# design.net
KiCad netlist of a schematic drawn in Altium Designer
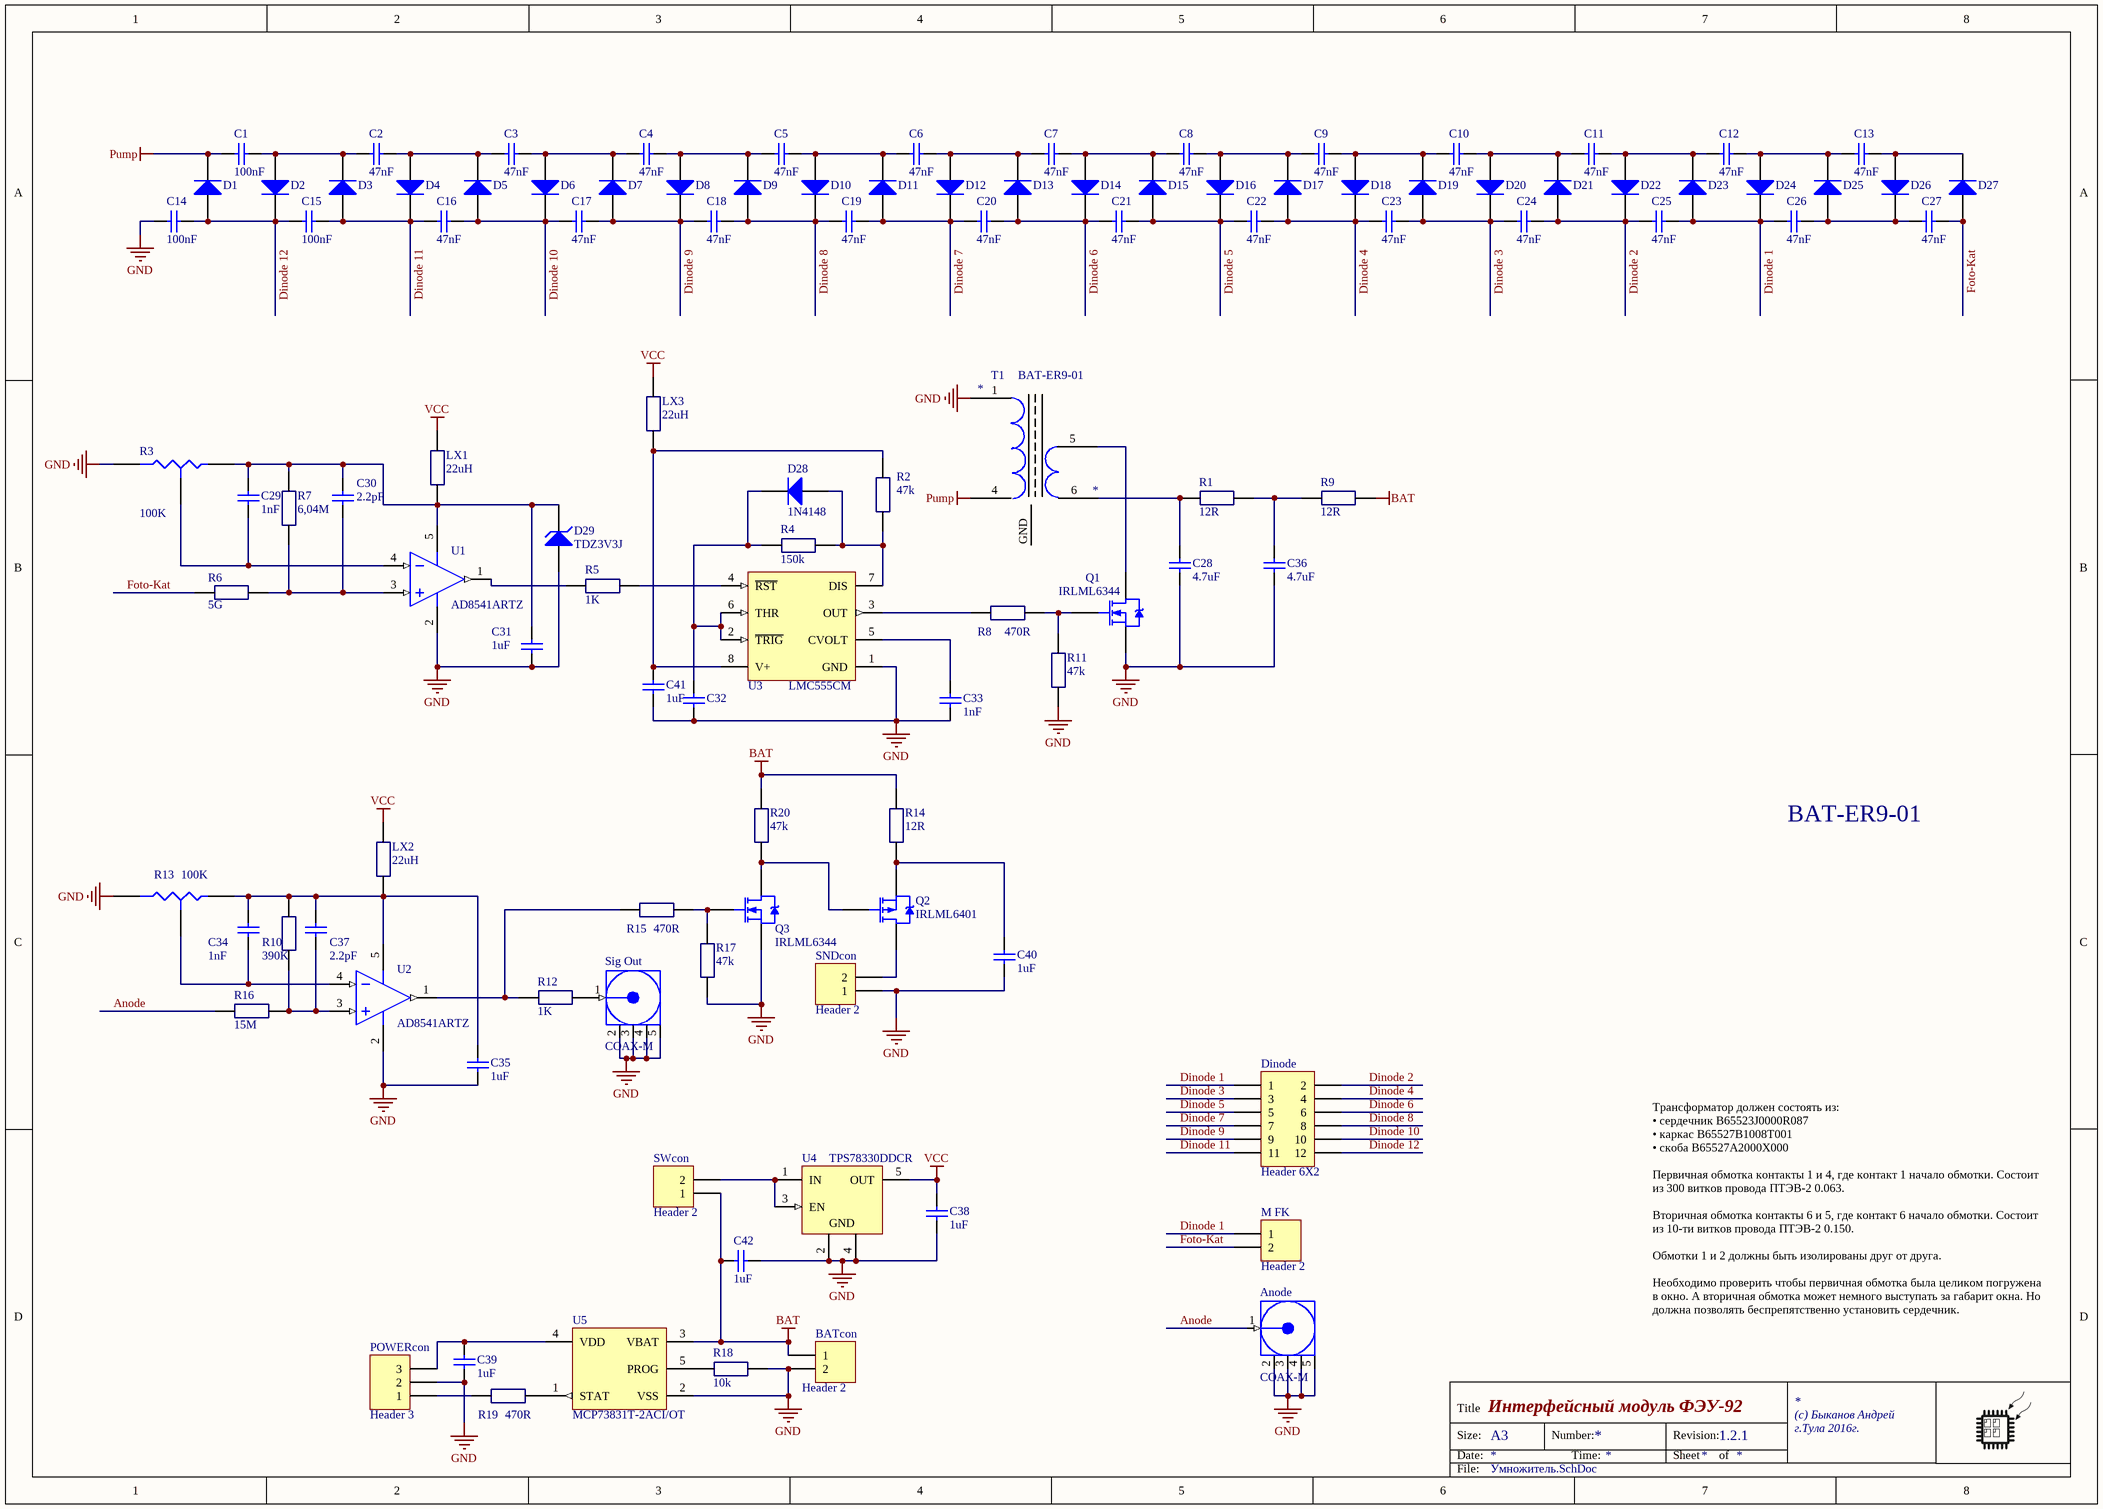
[diagram p0: Умножитель.SchDoc]

(export (version "E")
  (design (tool "Eeschema 10.0.6"))
  (components
    (comp (ref "Anode")
      (value "COAX-M")
      (footprint "MMCX2.54-V5")
      (description "RF Coaxial PCB Connector, MMCX; Thru-Hole, Vertical Mount Plug,  50 Ohm Impedance")
      (fields (field (name "PUBLISHER") "Altium Limited"))
      (libsource (lib "Miscellaneous Connectors") (part "COAX-M"))
    )
    (comp (ref "BATcon")
      (value "Header 2")
      (footprint "LIR2430")
      (description "Header, 2-Pin")
      (fields (field (name "PUBLISHER") "Altium Limited"))
      (libsource (lib "") (part "Header 2_1"))
    )
    (comp (ref "C1")
      (value "100nF")
      (footprint "Miscellaneous Devices:C1206")
      (description "Capacitor (Semiconductor SIM Model)")
      (fields (field (name "PUBLISHER") "Altium Limited"))
      (libsource (lib "Miscellaneous Devices") (part "Cap Semi"))
    )
    (comp (ref "C2")
      (value "47nF")
      (footprint "0805_CAP")
      (description "Capacitor (Semiconductor SIM Model)")
      (fields (field (name "PUBLISHER") "Altium Limited"))
      (libsource (lib "Miscellaneous Devices") (part "Cap Semi"))
    )
    (comp (ref "C3")
      (value "47nF")
      (footprint "0805_CAP")
      (description "Capacitor (Semiconductor SIM Model)")
      (fields (field (name "PUBLISHER") "Altium Limited"))
      (libsource (lib "Miscellaneous Devices") (part "Cap Semi"))
    )
    (comp (ref "C4")
      (value "47nF")
      (footprint "0805_CAP")
      (description "Capacitor (Semiconductor SIM Model)")
      (fields (field (name "PUBLISHER") "Altium Limited"))
      (libsource (lib "Miscellaneous Devices") (part "Cap Semi"))
    )
    (comp (ref "C5")
      (value "47nF")
      (footprint "0805_CAP")
      (description "Capacitor (Semiconductor SIM Model)")
      (fields (field (name "PUBLISHER") "Altium Limited"))
      (libsource (lib "Miscellaneous Devices") (part "Cap Semi"))
    )
    (comp (ref "C6")
      (value "47nF")
      (footprint "0805_CAP")
      (description "Capacitor (Semiconductor SIM Model)")
      (fields (field (name "PUBLISHER") "Altium Limited"))
      (libsource (lib "Miscellaneous Devices") (part "Cap Semi"))
    )
    (comp (ref "C7")
      (value "47nF")
      (footprint "0805_CAP")
      (description "Capacitor (Semiconductor SIM Model)")
      (fields (field (name "PUBLISHER") "Altium Limited"))
      (libsource (lib "Miscellaneous Devices") (part "Cap Semi"))
    )
    (comp (ref "C8")
      (value "47nF")
      (footprint "0805_CAP")
      (description "Capacitor (Semiconductor SIM Model)")
      (fields (field (name "PUBLISHER") "Altium Limited"))
      (libsource (lib "Miscellaneous Devices") (part "Cap Semi"))
    )
    (comp (ref "C9")
      (value "47nF")
      (footprint "0805_CAP")
      (description "Capacitor (Semiconductor SIM Model)")
      (fields (field (name "PUBLISHER") "Altium Limited"))
      (libsource (lib "Miscellaneous Devices") (part "Cap Semi"))
    )
    (comp (ref "C10")
      (value "47nF")
      (footprint "0805_CAP")
      (description "Capacitor (Semiconductor SIM Model)")
      (fields (field (name "PUBLISHER") "Altium Limited"))
      (libsource (lib "Miscellaneous Devices") (part "Cap Semi"))
    )
    (comp (ref "C11")
      (value "47nF")
      (footprint "0805_CAP")
      (description "Capacitor (Semiconductor SIM Model)")
      (fields (field (name "PUBLISHER") "Altium Limited"))
      (libsource (lib "Miscellaneous Devices") (part "Cap Semi"))
    )
    (comp (ref "C12")
      (value "47nF")
      (footprint "0805_CAP")
      (description "Capacitor (Semiconductor SIM Model)")
      (fields (field (name "PUBLISHER") "Altium Limited"))
      (libsource (lib "Miscellaneous Devices") (part "Cap Semi"))
    )
    (comp (ref "C13")
      (value "47nF")
      (footprint "0805_CAP")
      (description "Capacitor (Semiconductor SIM Model)")
      (fields (field (name "PUBLISHER") "Altium Limited"))
      (libsource (lib "Miscellaneous Devices") (part "Cap Semi"))
    )
    (comp (ref "C14")
      (value "100nF")
      (footprint "Miscellaneous Devices:C1206")
      (description "Capacitor (Semiconductor SIM Model)")
      (fields (field (name "PUBLISHER") "Altium Limited"))
      (libsource (lib "Miscellaneous Devices") (part "Cap Semi"))
    )
    (comp (ref "C15")
      (value "100nF")
      (footprint "Miscellaneous Devices:C1206")
      (description "Capacitor (Semiconductor SIM Model)")
      (fields (field (name "PUBLISHER") "Altium Limited"))
      (libsource (lib "Miscellaneous Devices") (part "Cap Semi"))
    )
    (comp (ref "C16")
      (value "47nF")
      (footprint "0805_CAP")
      (description "Capacitor (Semiconductor SIM Model)")
      (fields (field (name "PUBLISHER") "Altium Limited"))
      (libsource (lib "Miscellaneous Devices") (part "Cap Semi"))
    )
    (comp (ref "C17")
      (value "47nF")
      (footprint "0805_CAP")
      (description "Capacitor (Semiconductor SIM Model)")
      (fields (field (name "PUBLISHER") "Altium Limited"))
      (libsource (lib "Miscellaneous Devices") (part "Cap Semi"))
    )
    (comp (ref "C18")
      (value "47nF")
      (footprint "0805_CAP")
      (description "Capacitor (Semiconductor SIM Model)")
      (fields (field (name "PUBLISHER") "Altium Limited"))
      (libsource (lib "Miscellaneous Devices") (part "Cap Semi"))
    )
    (comp (ref "C19")
      (value "47nF")
      (footprint "0805_CAP")
      (description "Capacitor (Semiconductor SIM Model)")
      (fields (field (name "PUBLISHER") "Altium Limited"))
      (libsource (lib "Miscellaneous Devices") (part "Cap Semi"))
    )
    (comp (ref "C20")
      (value "47nF")
      (footprint "0805_CAP")
      (description "Capacitor (Semiconductor SIM Model)")
      (fields (field (name "PUBLISHER") "Altium Limited"))
      (libsource (lib "Miscellaneous Devices") (part "Cap Semi"))
    )
    (comp (ref "C21")
      (value "47nF")
      (footprint "0805_CAP")
      (description "Capacitor (Semiconductor SIM Model)")
      (fields (field (name "PUBLISHER") "Altium Limited"))
      (libsource (lib "Miscellaneous Devices") (part "Cap Semi"))
    )
    (comp (ref "C22")
      (value "47nF")
      (footprint "0805_CAP")
      (description "Capacitor (Semiconductor SIM Model)")
      (fields (field (name "PUBLISHER") "Altium Limited"))
      (libsource (lib "Miscellaneous Devices") (part "Cap Semi"))
    )
    (comp (ref "C23")
      (value "47nF")
      (footprint "0805_CAP")
      (description "Capacitor (Semiconductor SIM Model)")
      (fields (field (name "PUBLISHER") "Altium Limited"))
      (libsource (lib "Miscellaneous Devices") (part "Cap Semi"))
    )
    (comp (ref "C24")
      (value "47nF")
      (footprint "0805_CAP")
      (description "Capacitor (Semiconductor SIM Model)")
      (fields (field (name "PUBLISHER") "Altium Limited"))
      (libsource (lib "Miscellaneous Devices") (part "Cap Semi"))
    )
    (comp (ref "C25")
      (value "47nF")
      (footprint "0805_CAP")
      (description "Capacitor (Semiconductor SIM Model)")
      (fields (field (name "PUBLISHER") "Altium Limited"))
      (libsource (lib "Miscellaneous Devices") (part "Cap Semi"))
    )
    (comp (ref "C26")
      (value "47nF")
      (footprint "0805_CAP")
      (description "Capacitor (Semiconductor SIM Model)")
      (fields (field (name "PUBLISHER") "Altium Limited"))
      (libsource (lib "Miscellaneous Devices") (part "Cap Semi"))
    )
    (comp (ref "C27")
      (value "47nF")
      (footprint "0805_CAP")
      (description "Capacitor (Semiconductor SIM Model)")
      (fields (field (name "PUBLISHER") "Altium Limited"))
      (libsource (lib "Miscellaneous Devices") (part "Cap Semi"))
    )
    (comp (ref "C28")
      (value "4.7uF")
      (footprint "Miscellaneous Devices:C1206")
      (description "Capacitor (Semiconductor SIM Model)")
      (fields (field (name "PUBLISHER") "Altium Limited"))
      (libsource (lib "Miscellaneous Devices") (part "Cap Semi"))
    )
    (comp (ref "C29")
      (value "1nF")
      (footprint "1608[0603]_CAP")
      (description "Capacitor (Semiconductor SIM Model)")
      (fields (field (name "PUBLISHER") "Altium Limited"))
      (libsource (lib "Miscellaneous Devices") (part "Cap Semi"))
    )
    (comp (ref "C30")
      (value "2.2pF")
      (footprint "1608[0603]_CAP")
      (description "Capacitor (Semiconductor SIM Model)")
      (fields (field (name "PUBLISHER") "Altium Limited"))
      (libsource (lib "Miscellaneous Devices") (part "Cap Semi"))
    )
    (comp (ref "C31")
      (value "1uF")
      (footprint "1608[0603]_CAP")
      (description "Capacitor (Semiconductor SIM Model)")
      (fields (field (name "PUBLISHER") "Altium Limited"))
      (libsource (lib "Miscellaneous Devices") (part "Cap Semi"))
    )
    (comp (ref "C32")
      (value "220pF")
      (footprint "1608[0603]_CAP")
      (description "Capacitor (Semiconductor SIM Model)")
      (fields (field (name "PUBLISHER") "Altium Limited"))
      (libsource (lib "Miscellaneous Devices") (part "Cap Semi"))
    )
    (comp (ref "C33")
      (value "1nF")
      (footprint "1608[0603]_CAP")
      (description "Capacitor (Semiconductor SIM Model)")
      (fields (field (name "PUBLISHER") "Altium Limited"))
      (libsource (lib "Miscellaneous Devices") (part "Cap Semi"))
    )
    (comp (ref "C34")
      (value "1nF")
      (footprint "1608[0603]_CAP")
      (description "Capacitor (Semiconductor SIM Model)")
      (fields (field (name "PUBLISHER") "Altium Limited"))
      (libsource (lib "Miscellaneous Devices") (part "Cap Semi"))
    )
    (comp (ref "C35")
      (value "1uF")
      (footprint "1608[0603]_CAP")
      (description "Capacitor (Semiconductor SIM Model)")
      (fields (field (name "PUBLISHER") "Altium Limited"))
      (libsource (lib "Miscellaneous Devices") (part "Cap Semi"))
    )
    (comp (ref "C36")
      (value "4.7uF")
      (footprint "Miscellaneous Devices:C1206")
      (description "Capacitor (Semiconductor SIM Model)")
      (fields (field (name "PUBLISHER") "Altium Limited"))
      (libsource (lib "Miscellaneous Devices") (part "Cap Semi"))
    )
    (comp (ref "C37")
      (value "2.2pF")
      (footprint "1608[0603]_CAP")
      (description "Capacitor (Semiconductor SIM Model)")
      (fields (field (name "PUBLISHER") "Altium Limited"))
      (libsource (lib "Miscellaneous Devices") (part "Cap Semi"))
    )
    (comp (ref "C38")
      (value "1uF")
      (footprint "1608[0603]_CAP")
      (description "Capacitor (Semiconductor SIM Model)")
      (fields (field (name "PUBLISHER") "Altium Limited"))
      (libsource (lib "Miscellaneous Devices") (part "Cap Semi"))
    )
    (comp (ref "C39")
      (value "1uF")
      (footprint "1608[0603]_CAP")
      (description "Capacitor (Semiconductor SIM Model)")
      (fields (field (name "PUBLISHER") "Altium Limited"))
      (libsource (lib "Miscellaneous Devices") (part "Cap Semi"))
    )
    (comp (ref "C40")
      (value "1uF")
      (footprint "1608[0603]_CAP")
      (description "Capacitor (Semiconductor SIM Model)")
      (fields (field (name "PUBLISHER") "Altium Limited"))
      (libsource (lib "Miscellaneous Devices") (part "Cap Semi"))
    )
    (comp (ref "C41")
      (value "1uF")
      (footprint "1608[0603]_CAP")
      (description "Capacitor (Semiconductor SIM Model)")
      (fields (field (name "PUBLISHER") "Altium Limited"))
      (libsource (lib "Miscellaneous Devices") (part "Cap Semi"))
    )
    (comp (ref "C42")
      (value "1uF")
      (footprint "1608[0603]_CAP")
      (description "Capacitor (Semiconductor SIM Model)")
      (fields (field (name "PUBLISHER") "Altium Limited"))
      (libsource (lib "Miscellaneous Devices") (part "Cap Semi"))
    )
    (comp (ref "D1")
      (value "~")
      (footprint "DA2JF8100L")
      (description "Default Diode")
      (fields (field (name "PUBLISHER") "Altium Limited"))
      (libsource (lib "Miscellaneous Devices") (part "Diode"))
    )
    (comp (ref "D2")
      (value "~")
      (footprint "DA2JF8100L")
      (description "Default Diode")
      (fields (field (name "PUBLISHER") "Altium Limited"))
      (libsource (lib "Miscellaneous Devices") (part "Diode"))
    )
    (comp (ref "D3")
      (value "~")
      (footprint "DA2JF8100L")
      (description "Default Diode")
      (fields (field (name "PUBLISHER") "Altium Limited"))
      (libsource (lib "Miscellaneous Devices") (part "Diode"))
    )
    (comp (ref "D4")
      (value "~")
      (footprint "DA2JF8100L")
      (description "Default Diode")
      (fields (field (name "PUBLISHER") "Altium Limited"))
      (libsource (lib "Miscellaneous Devices") (part "Diode"))
    )
    (comp (ref "D5")
      (value "~")
      (footprint "DA2JF8100L")
      (description "Default Diode")
      (fields (field (name "PUBLISHER") "Altium Limited"))
      (libsource (lib "Miscellaneous Devices") (part "Diode"))
    )
    (comp (ref "D6")
      (value "~")
      (footprint "DA2JF8100L")
      (description "Default Diode")
      (fields (field (name "PUBLISHER") "Altium Limited"))
      (libsource (lib "Miscellaneous Devices") (part "Diode"))
    )
    (comp (ref "D7")
      (value "~")
      (footprint "DA2JF8100L")
      (description "Default Diode")
      (fields (field (name "PUBLISHER") "Altium Limited"))
      (libsource (lib "Miscellaneous Devices") (part "Diode"))
    )
    (comp (ref "D8")
      (value "~")
      (footprint "DA2JF8100L")
      (description "Default Diode")
      (fields (field (name "PUBLISHER") "Altium Limited"))
      (libsource (lib "Miscellaneous Devices") (part "Diode"))
    )
    (comp (ref "D9")
      (value "~")
      (footprint "DA2JF8100L")
      (description "Default Diode")
      (fields (field (name "PUBLISHER") "Altium Limited"))
      (libsource (lib "Miscellaneous Devices") (part "Diode"))
    )
    (comp (ref "D10")
      (value "~")
      (footprint "DA2JF8100L")
      (description "Default Diode")
      (fields (field (name "PUBLISHER") "Altium Limited"))
      (libsource (lib "Miscellaneous Devices") (part "Diode"))
    )
    (comp (ref "D11")
      (value "~")
      (footprint "DA2JF8100L")
      (description "Default Diode")
      (fields (field (name "PUBLISHER") "Altium Limited"))
      (libsource (lib "Miscellaneous Devices") (part "Diode"))
    )
    (comp (ref "D12")
      (value "~")
      (footprint "DA2JF8100L")
      (description "Default Diode")
      (fields (field (name "PUBLISHER") "Altium Limited"))
      (libsource (lib "Miscellaneous Devices") (part "Diode"))
    )
    (comp (ref "D13")
      (value "~")
      (footprint "DA2JF8100L")
      (description "Default Diode")
      (fields (field (name "PUBLISHER") "Altium Limited"))
      (libsource (lib "Miscellaneous Devices") (part "Diode"))
    )
    (comp (ref "D14")
      (value "~")
      (footprint "DA2JF8100L")
      (description "Default Diode")
      (fields (field (name "PUBLISHER") "Altium Limited"))
      (libsource (lib "Miscellaneous Devices") (part "Diode"))
    )
    (comp (ref "D15")
      (value "~")
      (footprint "DA2JF8100L")
      (description "Default Diode")
      (fields (field (name "PUBLISHER") "Altium Limited"))
      (libsource (lib "Miscellaneous Devices") (part "Diode"))
    )
    (comp (ref "D16")
      (value "~")
      (footprint "DA2JF8100L")
      (description "Default Diode")
      (fields (field (name "PUBLISHER") "Altium Limited"))
      (libsource (lib "Miscellaneous Devices") (part "Diode"))
    )
    (comp (ref "D17")
      (value "~")
      (footprint "DA2JF8100L")
      (description "Default Diode")
      (fields (field (name "PUBLISHER") "Altium Limited"))
      (libsource (lib "Miscellaneous Devices") (part "Diode"))
    )
    (comp (ref "D18")
      (value "~")
      (footprint "DA2JF8100L")
      (description "Default Diode")
      (fields (field (name "PUBLISHER") "Altium Limited"))
      (libsource (lib "Miscellaneous Devices") (part "Diode"))
    )
    (comp (ref "D19")
      (value "~")
      (footprint "DA2JF8100L")
      (description "Default Diode")
      (fields (field (name "PUBLISHER") "Altium Limited"))
      (libsource (lib "Miscellaneous Devices") (part "Diode"))
    )
    (comp (ref "D20")
      (value "~")
      (footprint "DA2JF8100L")
      (description "Default Diode")
      (fields (field (name "PUBLISHER") "Altium Limited"))
      (libsource (lib "Miscellaneous Devices") (part "Diode"))
    )
    (comp (ref "D21")
      (value "~")
      (footprint "DA2JF8100L")
      (description "Default Diode")
      (fields (field (name "PUBLISHER") "Altium Limited"))
      (libsource (lib "Miscellaneous Devices") (part "Diode"))
    )
    (comp (ref "D22")
      (value "~")
      (footprint "DA2JF8100L")
      (description "Default Diode")
      (fields (field (name "PUBLISHER") "Altium Limited"))
      (libsource (lib "Miscellaneous Devices") (part "Diode"))
    )
    (comp (ref "D23")
      (value "~")
      (footprint "DA2JF8100L")
      (description "Default Diode")
      (fields (field (name "PUBLISHER") "Altium Limited"))
      (libsource (lib "Miscellaneous Devices") (part "Diode"))
    )
    (comp (ref "D24")
      (value "~")
      (footprint "DA2JF8100L")
      (description "Default Diode")
      (fields (field (name "PUBLISHER") "Altium Limited"))
      (libsource (lib "Miscellaneous Devices") (part "Diode"))
    )
    (comp (ref "D25")
      (value "~")
      (footprint "DA2JF8100L")
      (description "Default Diode")
      (fields (field (name "PUBLISHER") "Altium Limited"))
      (libsource (lib "Miscellaneous Devices") (part "Diode"))
    )
    (comp (ref "D26")
      (value "~")
      (footprint "DA2JF8100L")
      (description "Default Diode")
      (fields (field (name "PUBLISHER") "Altium Limited"))
      (libsource (lib "Miscellaneous Devices") (part "Diode"))
    )
    (comp (ref "D27")
      (value "~")
      (footprint "DA2JF8100L")
      (description "Default Diode")
      (fields (field (name "PUBLISHER") "Altium Limited"))
      (libsource (lib "Miscellaneous Devices") (part "Diode"))
    )
    (comp (ref "D28")
      (value "1N4148")
      (footprint "GRZZ0002ZB-A")
      (description "Silicon Epitaxial Planar Diode for Various Detector, Modulator, Demodulator")
      (fields (field (name "PUBLISHER") "Altium Limited"))
      (libsource (lib "Renesas Diode") (part "1N4148"))
    )
    (comp (ref "D29")
      (value "TDZ3V3J")
      (footprint "SC-90")
      (description "Zener Diode")
      (fields (field (name "PUBLISHER") "Altium Limited"))
      (libsource (lib "Miscellaneous Devices") (part "D Zener"))
    )
    (comp (ref "Dinode")
      (value "Header 6X2")
      (footprint "HDR2X6")
      (description "Header, 6-Pin, Dual row")
      (fields (field (name "PUBLISHER") "Altium Limited"))
      (libsource (lib "Miscellaneous Connectors") (part "Header 6X2"))
    )
    (comp (ref "LX1")
      (value "22uH")
      (footprint "Resistor")
      (libsource (lib "Микрон-3") (part "Resistor 0805"))
    )
    (comp (ref "LX2")
      (value "22uH")
      (footprint "Resistor")
      (libsource (lib "Микрон-3") (part "Resistor 0805"))
    )
    (comp (ref "LX3")
      (value "22uH")
      (footprint "Resistor")
      (libsource (lib "Микрон-3") (part "Resistor 0805"))
    )
    (comp (ref "M FK")
      (value "Header 2")
      (footprint "HDR1X2")
      (description "Header, 2-Pin")
      (fields (field (name "PUBLISHER") "Altium Limited"))
      (libsource (lib "") (part "Header 2_1"))
    )
    (comp (ref "POWERcon")
      (value "Header 3")
      (footprint "HDR1X3")
      (description "Header, 3-Pin")
      (fields (field (name "PUBLISHER") "Altium Limited"))
      (libsource (lib "Miscellaneous Connectors") (part "Header 3"))
    )
    (comp (ref "Q1")
      (value "IRLML6344")
      (footprint "SOT-23_N")
      (description "HEXFET Power MOSFET")
      (fields (field (name "PUBLISHER") "Altium Limited"))
      (libsource (lib "IR Discrete MOSFET - Power") (part "IRLML2402"))
    )
    (comp (ref "Q2")
      (value "IRLML6401")
      (footprint "Micro3_N")
      (description "HEXFET Power MOSFET")
      (fields (field (name "PUBLISHER") "Altium Limited"))
      (libsource (lib "IR Discrete MOSFET - Power") (part "IRLML6401"))
    )
    (comp (ref "Q3")
      (value "IRLML6344")
      (footprint "SOT-23_N")
      (description "HEXFET Power MOSFET")
      (fields (field (name "PUBLISHER") "Altium Limited"))
      (libsource (lib "IR Discrete MOSFET - Power") (part "IRLML2402"))
    )
    (comp (ref "R1")
      (value "12R")
      (footprint "1608[0603]_RES")
      (libsource (lib "Микрон-3") (part "Resistor 0805"))
    )
    (comp (ref "R2")
      (value "47k")
      (footprint "1608[0603]_RES")
      (libsource (lib "Микрон-3") (part "Resistor 0805"))
    )
    (comp (ref "R3")
      (value "100K")
      (footprint "3223W")
      (description "Tapped Resistor")
      (fields (field (name "PUBLISHER") "Altium Limited"))
      (libsource (lib "Miscellaneous Devices") (part "Res Tap"))
    )
    (comp (ref "R4")
      (value "150k")
      (footprint "1608[0603]_RES")
      (libsource (lib "Микрон-3") (part "Resistor 0805"))
    )
    (comp (ref "R5")
      (value "1K")
      (footprint "1608[0603]")
      (libsource (lib "Микрон-3") (part "Resistor 0805"))
    )
    (comp (ref "R6")
      (value "5G")
      (footprint "HVF2512T5007FE")
      (libsource (lib "Микрон-3") (part "Resistor 0805"))
    )
    (comp (ref "R7")
      (value "6,04M")
      (footprint "1608[0603]")
      (libsource (lib "Микрон-3") (part "Resistor 0805"))
    )
    (comp (ref "R8")
      (value "470R")
      (footprint "1608[0603]_RES")
      (libsource (lib "Микрон-3") (part "Resistor 0805"))
    )
    (comp (ref "R9")
      (value "12R")
      (footprint "1608[0603]_RES")
      (libsource (lib "Микрон-3") (part "Resistor 0805"))
    )
    (comp (ref "R10")
      (value "390K")
      (footprint "1608[0603]")
      (libsource (lib "Микрон-3") (part "Resistor 0805"))
    )
    (comp (ref "R11")
      (value "47k")
      (footprint "1608[0603]_RES")
      (libsource (lib "Микрон-3") (part "Resistor 0805"))
    )
    (comp (ref "R12")
      (value "1K")
      (footprint "1608[0603]")
      (libsource (lib "Микрон-3") (part "Resistor 0805"))
    )
    (comp (ref "R13")
      (value "100K")
      (footprint "3223W")
      (description "Tapped Resistor")
      (fields (field (name "PUBLISHER") "Altium Limited"))
      (libsource (lib "Miscellaneous Devices") (part "Res Tap"))
    )
    (comp (ref "R14")
      (value "12R")
      (footprint "1608[0603]_RES")
      (libsource (lib "Микрон-3") (part "Resistor 0805"))
    )
    (comp (ref "R15")
      (value "470R")
      (footprint "1608[0603]_RES")
      (libsource (lib "Микрон-3") (part "Resistor 0805"))
    )
    (comp (ref "R16")
      (value "15M")
      (footprint "1608[0603]")
      (libsource (lib "Микрон-3") (part "Resistor 0805"))
    )
    (comp (ref "R17")
      (value "47k")
      (footprint "1608[0603]_RES")
      (libsource (lib "Микрон-3") (part "Resistor 0805"))
    )
    (comp (ref "R18")
      (value "10k")
      (footprint "1608[0603]_RES")
      (libsource (lib "Микрон-3") (part "Resistor 0805"))
    )
    (comp (ref "R19")
      (value "470R")
      (footprint "1608[0603]_RES")
      (libsource (lib "Микрон-3") (part "Resistor 0805"))
    )
    (comp (ref "R20")
      (value "47k")
      (footprint "1608[0603]_RES")
      (libsource (lib "Микрон-3") (part "Resistor 0805"))
    )
    (comp (ref "Sig Out")
      (value "COAX-M")
      (footprint "MMCX2.54-V5")
      (description "RF Coaxial PCB Connector, MMCX; Thru-Hole, Vertical Mount Plug,  50 Ohm Impedance")
      (fields (field (name "PUBLISHER") "Altium Limited"))
      (libsource (lib "Miscellaneous Connectors") (part "COAX-M"))
    )
    (comp (ref "SNDcon")
      (value "Header 2")
      (footprint "HDR1X2")
      (description "Header, 2-Pin")
      (fields (field (name "PUBLISHER") "Altium Limited"))
      (libsource (lib "Miscellaneous Connectors") (part "Header 2"))
    )
    (comp (ref "SWcon")
      (value "Header 2")
      (footprint "HDR1X2")
      (description "Header, 2-Pin")
      (fields (field (name "PUBLISHER") "Altium Limited"))
      (libsource (lib "Miscellaneous Connectors") (part "Header 2"))
    )
    (comp (ref "T1")
      (value "BAT-ER9-01")
      (footprint "Epcos ER9.5/5")
      (libsource (lib "My SCH library") (part "Epcos ER9.5/5"))
    )
    (comp (ref "U1")
      (value "AD8541ARTZ")
      (footprint "ADI-RJ-5_N")
      (fields
        (field (name "GENERIC PART NUMBER") "AD8541")
        (field (name "MANUFACTURER") "Analog Devices")
        (field (name "PARTNUMBER") "AD8541ARTZ-R2")
      )
      (libsource (lib "Analog Devices Operational Amplifiers") (part "AD8541ARTZ-R2"))
    )
    (comp (ref "U2")
      (value "AD8541ARTZ")
      (footprint "ADI-RJ-5_N")
      (fields
        (field (name "GENERIC PART NUMBER") "AD8541")
        (field (name "MANUFACTURER") "Analog Devices")
        (field (name "PARTNUMBER") "AD8541ARTZ-R2")
      )
      (libsource (lib "Analog Devices Operational Amplifiers") (part "AD8541ARTZ-R2"))
    )
    (comp (ref "U3")
      (value "LMC555CM")
      (footprint "M08A_N")
      (description "CMOS Timer, 8-pin Narrow SOIC")
      (fields
        (field (name "MANUFACTURER") "National Semiconductor")
        (field (name "PUBLISHER") "Altium Limited")
      )
      (libsource (lib "NSC Analog") (part "LMC555CM"))
    )
    (comp (ref "U4")
      (value "TPS78330DDCR")
      (footprint "TI-DDC5_N")
      (fields (field (name "MANUFACTURER") "Texas Instruments"))
      (libsource (lib "TI Power Management Linear Regulator Single Channel LDO (0-350mA)") (part "TPS78330DDCR"))
    )
    (comp (ref "U5")
      (value "MCP73831T-2ACI/OT")
      (footprint "SOT-23-OT5_N")
      (fields (field (name "PUBLISHER") "Altium Limited"))
      (libsource (lib "Microchip Power Mgt Battery Management") (part "MCP73831T-2ACI/OT"))
    )
  )
  (nets
    (net (code "1") (name "/Anode") (class "Default")
      (node (ref "Anode") (pin "1") (pinfunction "Signal_1") (pintype "input"))
      (node (ref "R16") (pin "1") (pinfunction "A_1") (pintype "passive"))
    )
    (net (code "2") (name "/Dinode 1") (class "Default")
      (node (ref "C25") (pin "1") (pinfunction "1_1") (pintype "passive"))
      (node (ref "C26") (pin "2") (pinfunction "2_2") (pintype "passive"))
      (node (ref "D23") (pin "1") (pinfunction "A_1") (pintype "passive"))
      (node (ref "D24") (pin "2") (pinfunction "K_2") (pintype "passive"))
      (node (ref "Dinode") (pin "1") (pinfunction "1_1") (pintype "passive"))
      (node (ref "M FK") (pin "1") (pinfunction "1_1") (pintype "passive"))
    )
    (net (code "3") (name "/Dinode 2") (class "Default")
      (node (ref "C24") (pin "1") (pinfunction "1_1") (pintype "passive"))
      (node (ref "C25") (pin "2") (pinfunction "2_2") (pintype "passive"))
      (node (ref "D21") (pin "1") (pinfunction "A_1") (pintype "passive"))
      (node (ref "D22") (pin "2") (pinfunction "K_2") (pintype "passive"))
      (node (ref "Dinode") (pin "2") (pinfunction "2_2") (pintype "passive"))
    )
    (net (code "4") (name "/Dinode 3") (class "Default")
      (node (ref "C23") (pin "1") (pinfunction "1_1") (pintype "passive"))
      (node (ref "C24") (pin "2") (pinfunction "2_2") (pintype "passive"))
      (node (ref "D19") (pin "1") (pinfunction "A_1") (pintype "passive"))
      (node (ref "D20") (pin "2") (pinfunction "K_2") (pintype "passive"))
      (node (ref "Dinode") (pin "3") (pinfunction "3_3") (pintype "passive"))
    )
    (net (code "5") (name "/Dinode 4") (class "Default")
      (node (ref "C22") (pin "1") (pinfunction "1_1") (pintype "passive"))
      (node (ref "C23") (pin "2") (pinfunction "2_2") (pintype "passive"))
      (node (ref "D17") (pin "1") (pinfunction "A_1") (pintype "passive"))
      (node (ref "D18") (pin "2") (pinfunction "K_2") (pintype "passive"))
      (node (ref "Dinode") (pin "4") (pinfunction "4_4") (pintype "passive"))
    )
    (net (code "6") (name "/Dinode 5") (class "Default")
      (node (ref "C21") (pin "1") (pinfunction "1_1") (pintype "passive"))
      (node (ref "C22") (pin "2") (pinfunction "2_2") (pintype "passive"))
      (node (ref "D15") (pin "1") (pinfunction "A_1") (pintype "passive"))
      (node (ref "D16") (pin "2") (pinfunction "K_2") (pintype "passive"))
      (node (ref "Dinode") (pin "5") (pinfunction "5_5") (pintype "passive"))
    )
    (net (code "7") (name "/Dinode 6") (class "Default")
      (node (ref "C20") (pin "1") (pinfunction "1_1") (pintype "passive"))
      (node (ref "C21") (pin "2") (pinfunction "2_2") (pintype "passive"))
      (node (ref "D13") (pin "1") (pinfunction "A_1") (pintype "passive"))
      (node (ref "D14") (pin "2") (pinfunction "K_2") (pintype "passive"))
      (node (ref "Dinode") (pin "6") (pinfunction "6_6") (pintype "passive"))
    )
    (net (code "8") (name "/Dinode 7") (class "Default")
      (node (ref "C19") (pin "1") (pinfunction "1_1") (pintype "passive"))
      (node (ref "C20") (pin "2") (pinfunction "2_2") (pintype "passive"))
      (node (ref "D11") (pin "1") (pinfunction "A_1") (pintype "passive"))
      (node (ref "D12") (pin "2") (pinfunction "K_2") (pintype "passive"))
      (node (ref "Dinode") (pin "7") (pinfunction "7_7") (pintype "passive"))
    )
    (net (code "9") (name "/Dinode 8") (class "Default")
      (node (ref "C18") (pin "1") (pinfunction "1_1") (pintype "passive"))
      (node (ref "C19") (pin "2") (pinfunction "2_2") (pintype "passive"))
      (node (ref "D10") (pin "2") (pinfunction "K_2") (pintype "passive"))
      (node (ref "D9") (pin "1") (pinfunction "A_1") (pintype "passive"))
      (node (ref "Dinode") (pin "8") (pinfunction "8_8") (pintype "passive"))
    )
    (net (code "10") (name "/Dinode 9") (class "Default")
      (node (ref "C17") (pin "1") (pinfunction "1_1") (pintype "passive"))
      (node (ref "C18") (pin "2") (pinfunction "2_2") (pintype "passive"))
      (node (ref "D7") (pin "1") (pinfunction "A_1") (pintype "passive"))
      (node (ref "D8") (pin "2") (pinfunction "K_2") (pintype "passive"))
      (node (ref "Dinode") (pin "9") (pinfunction "9_9") (pintype "passive"))
    )
    (net (code "11") (name "/Dinode 10") (class "Default")
      (node (ref "C16") (pin "1") (pinfunction "1_1") (pintype "passive"))
      (node (ref "C17") (pin "2") (pinfunction "2_2") (pintype "passive"))
      (node (ref "D5") (pin "1") (pinfunction "A_1") (pintype "passive"))
      (node (ref "D6") (pin "2") (pinfunction "K_2") (pintype "passive"))
      (node (ref "Dinode") (pin "10") (pinfunction "10_10") (pintype "passive"))
    )
    (net (code "12") (name "/Dinode 11") (class "Default")
      (node (ref "C15") (pin "1") (pinfunction "1_1") (pintype "passive"))
      (node (ref "C16") (pin "2") (pinfunction "2_2") (pintype "passive"))
      (node (ref "D3") (pin "1") (pinfunction "A_1") (pintype "passive"))
      (node (ref "D4") (pin "2") (pinfunction "K_2") (pintype "passive"))
      (node (ref "Dinode") (pin "11") (pinfunction "11_11") (pintype "passive"))
    )
    (net (code "13") (name "/Dinode 12") (class "Default")
      (node (ref "C14") (pin "1") (pinfunction "1_1") (pintype "passive"))
      (node (ref "C15") (pin "2") (pinfunction "2_2") (pintype "passive"))
      (node (ref "D1") (pin "1") (pinfunction "A_1") (pintype "passive"))
      (node (ref "D2") (pin "2") (pinfunction "K_2") (pintype "passive"))
      (node (ref "Dinode") (pin "12") (pinfunction "12_12") (pintype "passive"))
    )
    (net (code "14") (name "/Foto-Kat") (class "Default")
      (node (ref "C27") (pin "1") (pinfunction "1_1") (pintype "passive"))
      (node (ref "D27") (pin "1") (pinfunction "A_1") (pintype "passive"))
      (node (ref "M FK") (pin "2") (pinfunction "2_2") (pintype "passive"))
      (node (ref "R6") (pin "1") (pinfunction "A_1") (pintype "passive"))
    )
    (net (code "15") (name "BAT") (class "Default")
      (node (ref "BATcon") (pin "1") (pinfunction "1_1") (pintype "passive"))
      (node (ref "C42") (pin "2") (pinfunction "2_2") (pintype "passive"))
      (node (ref "R14") (pin "2") (pinfunction "2_2") (pintype "passive"))
      (node (ref "R20") (pin "1") (pinfunction "A_1") (pintype "passive"))
      (node (ref "R9") (pin "2") (pinfunction "2_2") (pintype "passive"))
      (node (ref "SWcon") (pin "1") (pinfunction "1_1") (pintype "passive"))
      (node (ref "U5") (pin "3") (pinfunction "VBAT_3") (pintype "power_in"))
    )
    (net (code "16") (name "GND") (class "Default")
      (node (ref "Anode") (pin "2") (pinfunction "GND_2") (pintype "power_in"))
      (node (ref "Anode") (pin "3") (pinfunction "GND_3") (pintype "power_in"))
      (node (ref "Anode") (pin "4") (pinfunction "GND_4") (pintype "power_in"))
      (node (ref "Anode") (pin "5") (pinfunction "GND_5") (pintype "power_in"))
      (node (ref "BATcon") (pin "2") (pinfunction "2_2") (pintype "passive"))
      (node (ref "C14") (pin "2") (pinfunction "2_2") (pintype "passive"))
      (node (ref "C28") (pin "2") (pinfunction "2_2") (pintype "passive"))
      (node (ref "C31") (pin "2") (pinfunction "2_2") (pintype "passive"))
      (node (ref "C32") (pin "1") (pinfunction "1_1") (pintype "passive"))
      (node (ref "C33") (pin "2") (pinfunction "2_2") (pintype "passive"))
      (node (ref "C35") (pin "2") (pinfunction "2_2") (pintype "passive"))
      (node (ref "C36") (pin "2") (pinfunction "2_2") (pintype "passive"))
      (node (ref "C38") (pin "1") (pinfunction "1_1") (pintype "passive"))
      (node (ref "C39") (pin "2") (pinfunction "2_2") (pintype "passive"))
      (node (ref "C40") (pin "2") (pinfunction "2_2") (pintype "passive"))
      (node (ref "C41") (pin "2") (pinfunction "2_2") (pintype "passive"))
      (node (ref "C42") (pin "1") (pinfunction "1_1") (pintype "passive"))
      (node (ref "D29") (pin "1") (pinfunction "A_1") (pintype "passive"))
      (node (ref "POWERcon") (pin "2") (pinfunction "2_2") (pintype "passive"))
      (node (ref "Q1") (pin "2") (pinfunction "S_2") (pintype "passive"))
      (node (ref "Q3") (pin "2") (pinfunction "S_2") (pintype "passive"))
      (node (ref "R11") (pin "1") (pinfunction "A_1") (pintype "passive"))
      (node (ref "R13") (pin "2") (pinfunction "B_2") (pintype "passive"))
      (node (ref "R17") (pin "2") (pinfunction "2_2") (pintype "passive"))
      (node (ref "R18") (pin "2") (pinfunction "2_2") (pintype "passive"))
      (node (ref "R3") (pin "2") (pinfunction "B_2") (pintype "passive"))
      (node (ref "SNDcon") (pin "1") (pinfunction "1_1") (pintype "passive"))
      (node (ref "Sig Out") (pin "2") (pinfunction "GND_2") (pintype "power_in"))
      (node (ref "Sig Out") (pin "3") (pinfunction "GND_3") (pintype "power_in"))
      (node (ref "Sig Out") (pin "4") (pinfunction "GND_4") (pintype "power_in"))
      (node (ref "Sig Out") (pin "5") (pinfunction "GND_5") (pintype "power_in"))
      (node (ref "T1") (pin "1") (pinfunction "1_1") (pintype "passive"))
      (node (ref "U1") (pin "2") (pinfunction "-V_2") (pintype "power_in"))
      (node (ref "U2") (pin "2") (pinfunction "-V_2") (pintype "power_in"))
      (node (ref "U3") (pin "1") (pinfunction "GND_1") (pintype "power_in"))
      (node (ref "U4") (pin "2") (pinfunction "GND_2") (pintype "power_in"))
      (node (ref "U4") (pin "4") (pinfunction "GND_4") (pintype "power_in"))
      (node (ref "U5") (pin "2") (pinfunction "VSS_2") (pintype "power_in"))
    )
    (net (code "17") (name "Net-(D2-A)") (class "Default")
      (node (ref "C1") (pin "1") (pinfunction "1_1") (pintype "passive"))
      (node (ref "C2") (pin "2") (pinfunction "2_2") (pintype "passive"))
      (node (ref "D2") (pin "1") (pinfunction "A_1") (pintype "passive"))
      (node (ref "D3") (pin "2") (pinfunction "K_2") (pintype "passive"))
    )
    (net (code "18") (name "Net-(D4-A)") (class "Default")
      (node (ref "C2") (pin "1") (pinfunction "1_1") (pintype "passive"))
      (node (ref "C3") (pin "2") (pinfunction "2_2") (pintype "passive"))
      (node (ref "D4") (pin "1") (pinfunction "A_1") (pintype "passive"))
      (node (ref "D5") (pin "2") (pinfunction "K_2") (pintype "passive"))
    )
    (net (code "19") (name "Net-(D6-A)") (class "Default")
      (node (ref "C3") (pin "1") (pinfunction "1_1") (pintype "passive"))
      (node (ref "C4") (pin "2") (pinfunction "2_2") (pintype "passive"))
      (node (ref "D6") (pin "1") (pinfunction "A_1") (pintype "passive"))
      (node (ref "D7") (pin "2") (pinfunction "K_2") (pintype "passive"))
    )
    (net (code "20") (name "Net-(D8-A)") (class "Default")
      (node (ref "C4") (pin "1") (pinfunction "1_1") (pintype "passive"))
      (node (ref "C5") (pin "2") (pinfunction "2_2") (pintype "passive"))
      (node (ref "D8") (pin "1") (pinfunction "A_1") (pintype "passive"))
      (node (ref "D9") (pin "2") (pinfunction "K_2") (pintype "passive"))
    )
    (net (code "21") (name "Net-(D10-A)") (class "Default")
      (node (ref "C5") (pin "1") (pinfunction "1_1") (pintype "passive"))
      (node (ref "C6") (pin "2") (pinfunction "2_2") (pintype "passive"))
      (node (ref "D10") (pin "1") (pinfunction "A_1") (pintype "passive"))
      (node (ref "D11") (pin "2") (pinfunction "K_2") (pintype "passive"))
    )
    (net (code "22") (name "Net-(D12-A)") (class "Default")
      (node (ref "C6") (pin "1") (pinfunction "1_1") (pintype "passive"))
      (node (ref "C7") (pin "2") (pinfunction "2_2") (pintype "passive"))
      (node (ref "D12") (pin "1") (pinfunction "A_1") (pintype "passive"))
      (node (ref "D13") (pin "2") (pinfunction "K_2") (pintype "passive"))
    )
    (net (code "23") (name "Net-(D14-A)") (class "Default")
      (node (ref "C7") (pin "1") (pinfunction "1_1") (pintype "passive"))
      (node (ref "C8") (pin "2") (pinfunction "2_2") (pintype "passive"))
      (node (ref "D14") (pin "1") (pinfunction "A_1") (pintype "passive"))
      (node (ref "D15") (pin "2") (pinfunction "K_2") (pintype "passive"))
    )
    (net (code "24") (name "Net-(D16-A)") (class "Default")
      (node (ref "C8") (pin "1") (pinfunction "1_1") (pintype "passive"))
      (node (ref "C9") (pin "2") (pinfunction "2_2") (pintype "passive"))
      (node (ref "D16") (pin "1") (pinfunction "A_1") (pintype "passive"))
      (node (ref "D17") (pin "2") (pinfunction "K_2") (pintype "passive"))
    )
    (net (code "25") (name "Net-(D18-A)") (class "Default")
      (node (ref "C10") (pin "2") (pinfunction "2_2") (pintype "passive"))
      (node (ref "C9") (pin "1") (pinfunction "1_1") (pintype "passive"))
      (node (ref "D18") (pin "1") (pinfunction "A_1") (pintype "passive"))
      (node (ref "D19") (pin "2") (pinfunction "K_2") (pintype "passive"))
    )
    (net (code "26") (name "Net-(D20-A)") (class "Default")
      (node (ref "C10") (pin "1") (pinfunction "1_1") (pintype "passive"))
      (node (ref "C11") (pin "2") (pinfunction "2_2") (pintype "passive"))
      (node (ref "D20") (pin "1") (pinfunction "A_1") (pintype "passive"))
      (node (ref "D21") (pin "2") (pinfunction "K_2") (pintype "passive"))
    )
    (net (code "27") (name "Net-(D22-A)") (class "Default")
      (node (ref "C11") (pin "1") (pinfunction "1_1") (pintype "passive"))
      (node (ref "C12") (pin "2") (pinfunction "2_2") (pintype "passive"))
      (node (ref "D22") (pin "1") (pinfunction "A_1") (pintype "passive"))
      (node (ref "D23") (pin "2") (pinfunction "K_2") (pintype "passive"))
    )
    (net (code "28") (name "Net-(D24-A)") (class "Default")
      (node (ref "C12") (pin "1") (pinfunction "1_1") (pintype "passive"))
      (node (ref "C13") (pin "2") (pinfunction "2_2") (pintype "passive"))
      (node (ref "D24") (pin "1") (pinfunction "A_1") (pintype "passive"))
      (node (ref "D25") (pin "2") (pinfunction "K_2") (pintype "passive"))
    )
    (net (code "29") (name "Net-(D25-A)") (class "Default")
      (node (ref "C26") (pin "1") (pinfunction "1_1") (pintype "passive"))
      (node (ref "C27") (pin "2") (pinfunction "2_2") (pintype "passive"))
      (node (ref "D25") (pin "1") (pinfunction "A_1") (pintype "passive"))
      (node (ref "D26") (pin "2") (pinfunction "K_2") (pintype "passive"))
    )
    (net (code "30") (name "Net-(D26-A)") (class "Default")
      (node (ref "C13") (pin "1") (pinfunction "1_1") (pintype "passive"))
      (node (ref "D26") (pin "1") (pinfunction "A_1") (pintype "passive"))
      (node (ref "D27") (pin "2") (pinfunction "K_2") (pintype "passive"))
    )
    (net (code "31") (name "Net-(D28-A)") (class "Default")
      (node (ref "D28") (pin "2") (pinfunction "A_2") (pintype "passive"))
      (node (ref "R2") (pin "1") (pinfunction "A_1") (pintype "passive"))
      (node (ref "R4") (pin "2") (pinfunction "2_2") (pintype "passive"))
      (node (ref "U3") (pin "7") (pinfunction "DIS_7") (pintype "open_collector"))
    )
    (net (code "32") (name "Net-(D28-K)") (class "Default")
      (node (ref "C32") (pin "2") (pinfunction "2_2") (pintype "passive"))
      (node (ref "D28") (pin "1") (pinfunction "K_1") (pintype "passive"))
      (node (ref "R4") (pin "1") (pinfunction "A_1") (pintype "passive"))
      (node (ref "U3") (pin "2") (pinfunction "~{TRIG}_2") (pintype "input"))
      (node (ref "U3") (pin "6") (pinfunction "THR_6") (pintype "input"))
    )
    (net (code "33") (name "Net-(D29-K)") (class "Default")
      (node (ref "C29") (pin "1") (pinfunction "1_1") (pintype "passive"))
      (node (ref "C30") (pin "1") (pinfunction "1_1") (pintype "passive"))
      (node (ref "C31") (pin "1") (pinfunction "1_1") (pintype "passive"))
      (node (ref "D29") (pin "2") (pinfunction "K_2") (pintype "passive"))
      (node (ref "LX1") (pin "2") (pinfunction "2_2") (pintype "passive"))
      (node (ref "R3") (pin "1") (pinfunction "A_1") (pintype "passive"))
      (node (ref "R7") (pin "1") (pinfunction "A_1") (pintype "passive"))
      (node (ref "U1") (pin "5") (pinfunction "+V_5") (pintype "power_in"))
    )
    (net (code "34") (name "Net-(POWERcon-Pad1)") (class "Default")
      (node (ref "POWERcon") (pin "1") (pinfunction "1_1") (pintype "passive"))
      (node (ref "R19") (pin "2") (pinfunction "2_2") (pintype "passive"))
    )
    (net (code "35") (name "Net-(Q1-D)") (class "Default")
      (node (ref "Q1") (pin "3") (pinfunction "D_3") (pintype "passive"))
      (node (ref "T1") (pin "5") (pinfunction "5_5") (pintype "passive"))
    )
    (net (code "36") (name "Net-(Q1-G)") (class "Default")
      (node (ref "Q1") (pin "1") (pinfunction "G_1") (pintype "passive"))
      (node (ref "R11") (pin "2") (pinfunction "2_2") (pintype "passive"))
      (node (ref "R8") (pin "1") (pinfunction "A_1") (pintype "passive"))
    )
    (net (code "37") (name "Net-(Q2-D)") (class "Default")
      (node (ref "Q2") (pin "3") (pinfunction "D_3") (pintype "passive"))
      (node (ref "SNDcon") (pin "2") (pinfunction "2_2") (pintype "passive"))
    )
    (net (code "38") (name "Net-(Q2-G)") (class "Default")
      (node (ref "Q2") (pin "1") (pinfunction "G_1") (pintype "passive"))
      (node (ref "Q3") (pin "3") (pinfunction "D_3") (pintype "passive"))
      (node (ref "R20") (pin "2") (pinfunction "2_2") (pintype "passive"))
    )
    (net (code "39") (name "Net-(Q2-S)") (class "Default")
      (node (ref "C40") (pin "1") (pinfunction "1_1") (pintype "passive"))
      (node (ref "Q2") (pin "2") (pinfunction "S_2") (pintype "passive"))
      (node (ref "R14") (pin "1") (pinfunction "A_1") (pintype "passive"))
    )
    (net (code "40") (name "Net-(Q3-G)") (class "Default")
      (node (ref "Q3") (pin "1") (pinfunction "G_1") (pintype "passive"))
      (node (ref "R15") (pin "1") (pinfunction "A_1") (pintype "passive"))
      (node (ref "R17") (pin "1") (pinfunction "A_1") (pintype "passive"))
    )
    (net (code "41") (name "Net-(R1-A)") (class "Default")
      (node (ref "C28") (pin "1") (pinfunction "1_1") (pintype "passive"))
      (node (ref "R1") (pin "1") (pinfunction "A_1") (pintype "passive"))
      (node (ref "T1") (pin "6") (pintype "passive"))
    )
    (net (code "42") (name "Net-(R3-TAP)") (class "Default")
      (node (ref "C29") (pin "2") (pinfunction "2_2") (pintype "passive"))
      (node (ref "R3") (pin "3") (pinfunction "TAP_3") (pintype "passive"))
      (node (ref "U1") (pin "4") (pinfunction "-IN_A_4") (pintype "input"))
    )
    (net (code "43") (name "Net-(R5-A)") (class "Default")
      (node (ref "R5") (pin "1") (pinfunction "A_1") (pintype "passive"))
      (node (ref "U1") (pin "1") (pinfunction "OUT_A_1") (pintype "output"))
    )
    (net (code "44") (name "Net-(R9-A)") (class "Default")
      (node (ref "C36") (pin "1") (pinfunction "1_1") (pintype "passive"))
      (node (ref "R1") (pin "2") (pinfunction "2_2") (pintype "passive"))
      (node (ref "R9") (pin "1") (pinfunction "A_1") (pintype "passive"))
    )
    (net (code "45") (name "Net-(R10-A)") (class "Default")
      (node (ref "C37") (pin "2") (pinfunction "2_2") (pintype "passive"))
      (node (ref "R10") (pin "1") (pinfunction "A_1") (pintype "passive"))
      (node (ref "R16") (pin "2") (pinfunction "2_2") (pintype "passive"))
      (node (ref "U2") (pin "3") (pinfunction "+IN_A_3") (pintype "input"))
    )
    (net (code "46") (name "Net-(R12-A)") (class "Default")
      (node (ref "R12") (pin "1") (pinfunction "A_1") (pintype "passive"))
      (node (ref "Sig Out") (pin "1") (pinfunction "Signal_1") (pintype "input"))
    )
    (net (code "47") (name "Net-(R13-A)") (class "Default")
      (node (ref "C34") (pin "1") (pinfunction "1_1") (pintype "passive"))
      (node (ref "C35") (pin "1") (pinfunction "1_1") (pintype "passive"))
      (node (ref "C37") (pin "1") (pinfunction "1_1") (pintype "passive"))
      (node (ref "LX2") (pin "2") (pinfunction "2_2") (pintype "passive"))
      (node (ref "R10") (pin "2") (pinfunction "2_2") (pintype "passive"))
      (node (ref "R13") (pin "1") (pinfunction "A_1") (pintype "passive"))
      (node (ref "U2") (pin "5") (pinfunction "+V_5") (pintype "power_in"))
    )
    (net (code "48") (name "Net-(R13-TAP)") (class "Default")
      (node (ref "C34") (pin "2") (pinfunction "2_2") (pintype "passive"))
      (node (ref "R13") (pin "3") (pinfunction "TAP_3") (pintype "passive"))
      (node (ref "U2") (pin "4") (pinfunction "-IN_A_4") (pintype "input"))
    )
    (net (code "49") (name "Net-(R18-A)") (class "Default")
      (node (ref "R18") (pin "1") (pinfunction "A_1") (pintype "passive"))
      (node (ref "U5") (pin "5") (pinfunction "PROG_5") (pintype "passive"))
    )
    (net (code "50") (name "Net-(R19-A)") (class "Default")
      (node (ref "R19") (pin "1") (pinfunction "A_1") (pintype "passive"))
      (node (ref "U5") (pin "1") (pinfunction "STAT_1") (pintype "output"))
    )
    (net (code "51") (name "Net-(U1-+IN_A)") (class "Default")
      (node (ref "C30") (pin "2") (pinfunction "2_2") (pintype "passive"))
      (node (ref "R6") (pin "2") (pinfunction "2_2") (pintype "passive"))
      (node (ref "R7") (pin "2") (pinfunction "2_2") (pintype "passive"))
      (node (ref "U1") (pin "3") (pinfunction "+IN_A_3") (pintype "input"))
    )
    (net (code "52") (name "Net-(U2-OUT_A)") (class "Default")
      (node (ref "R12") (pin "2") (pinfunction "2_2") (pintype "passive"))
      (node (ref "R15") (pin "2") (pinfunction "2_2") (pintype "passive"))
      (node (ref "U2") (pin "1") (pinfunction "OUT_A_1") (pintype "output"))
    )
    (net (code "53") (name "Net-(U3-CVOLT)") (class "Default")
      (node (ref "C33") (pin "1") (pinfunction "1_1") (pintype "passive"))
      (node (ref "U3") (pin "5") (pinfunction "CVOLT_5") (pintype "passive"))
    )
    (net (code "54") (name "Net-(U3-OUT)") (class "Default")
      (node (ref "R8") (pin "2") (pinfunction "2_2") (pintype "passive"))
      (node (ref "U3") (pin "3") (pinfunction "OUT_3") (pintype "output"))
    )
    (net (code "55") (name "Net-(U3-V+)") (class "Default")
      (node (ref "C41") (pin "1") (pinfunction "1_1") (pintype "passive"))
      (node (ref "LX3") (pin "2") (pinfunction "2_2") (pintype "passive"))
      (node (ref "R2") (pin "2") (pinfunction "2_2") (pintype "passive"))
      (node (ref "U3") (pin "8") (pinfunction "V+_8") (pintype "power_in"))
    )
    (net (code "56") (name "Net-(U3-~{RST})") (class "Default")
      (node (ref "R5") (pin "2") (pinfunction "2_2") (pintype "passive"))
      (node (ref "U3") (pin "4") (pinfunction "~{RST}_4") (pintype "input"))
    )
    (net (code "57") (name "Net-(U4-EN)") (class "Default")
      (node (ref "SWcon") (pin "2") (pinfunction "2_2") (pintype "passive"))
      (node (ref "U4") (pin "1") (pinfunction "IN_1") (pintype "power_in"))
      (node (ref "U4") (pin "3") (pinfunction "EN_3") (pintype "input"))
    )
    (net (code "58") (name "Net-(U5-VDD)") (class "Default")
      (node (ref "C39") (pin "1") (pinfunction "1_1") (pintype "passive"))
      (node (ref "POWERcon") (pin "3") (pinfunction "3_3") (pintype "passive"))
      (node (ref "U5") (pin "4") (pinfunction "VDD_4") (pintype "power_in"))
    )
    (net (code "59") (name "Pump") (class "Default")
      (node (ref "C1") (pin "2") (pinfunction "2_2") (pintype "passive"))
      (node (ref "D1") (pin "2") (pinfunction "K_2") (pintype "passive"))
      (node (ref "T1") (pin "4") (pinfunction "4_4") (pintype "passive"))
    )
    (net (code "60") (name "VCC") (class "Default")
      (node (ref "C38") (pin "2") (pinfunction "2_2") (pintype "passive"))
      (node (ref "LX1") (pin "1") (pinfunction "A_1") (pintype "passive"))
      (node (ref "LX2") (pin "1") (pinfunction "A_1") (pintype "passive"))
      (node (ref "LX3") (pin "1") (pinfunction "A_1") (pintype "passive"))
      (node (ref "U4") (pin "5") (pinfunction "OUT_5") (pintype "power_in"))
    )
    (net (code "61") (name "unconnected-(T1-PadGND)") (class "Default")
      (node (ref "T1") (pin "GND") (pinfunction "GND_GND") (pintype "passive"))
    )
  )
)
